# ControllerBoardV2Schematic.net
KiCad netlist of a schematic drawn in Altium Designer
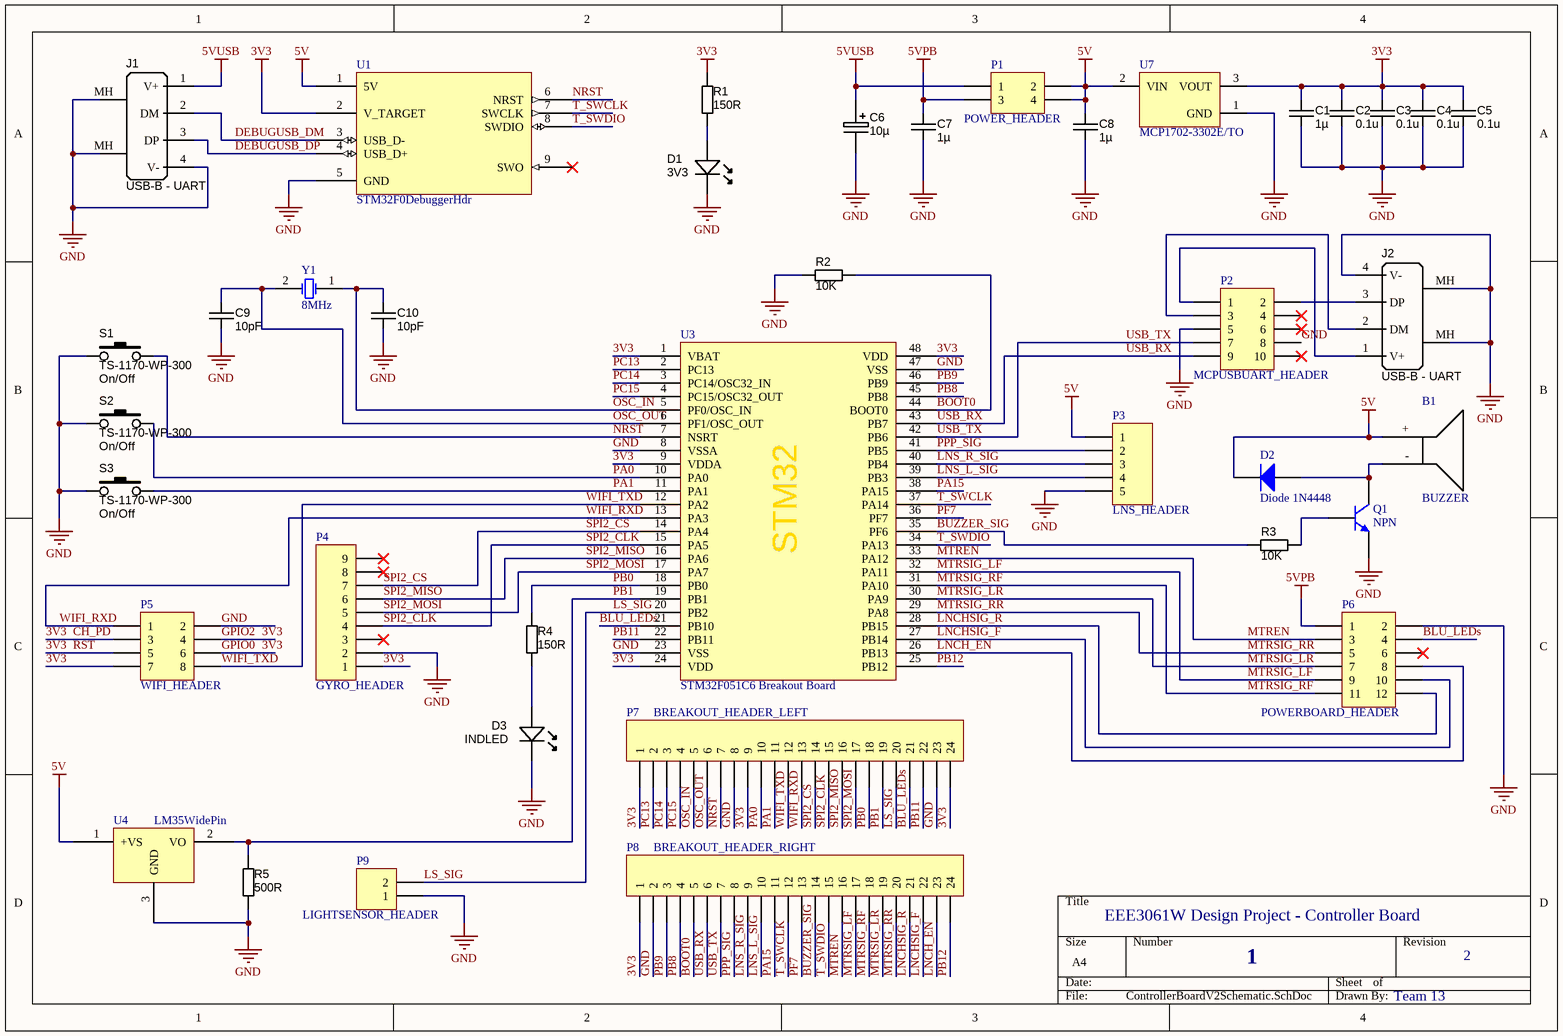
[diagram p0: ControllerBoardV2Schematic.SchDoc]

(export (version "E")
  (design (tool "Eeschema 10.0.6"))
  (components
    (comp (ref "B1")
      (value "BUZZER")
      (footprint "HCM1206UX-G")
      (description "2.3KHz Internally Driven Buzzer")
      (libsource (lib "ControllerBoardCMPV2") (part "HCM1206UX-G"))
    )
    (comp (ref "C1")
      (value "1µ")
      (footprint "CAPC3216X180N")
      (description "Capacitor SMD Cer 10uF 10% 16V X7R 1206")
      (fields (field (name "TOLERANCE") "±10%") (field (name "Comment") "approved sub OK"))
      (libsource (lib "PBL - Capacitors") (part "CAPC_10u_1206_16V"))
    )
    (comp (ref "C2")
      (value "0.1u")
      (footprint "CAPC2012X135N")
      (description "Capacitor SMD Cer 1.8nF 10% 50V X7R 0805")
      (fields (field (name "TOLERANCE") "±10%") (field (name "Comment") "approved sub OK"))
      (libsource (lib "PBL - Capacitors") (part "CAPC_1n8_50V_0805"))
    )
    (comp (ref "C3")
      (value "0.1u")
      (footprint "CAPC2012X135N")
      (description "Capacitor SMD Cer 1.8nF 10% 50V X7R 0805")
      (fields (field (name "TOLERANCE") "±10%") (field (name "Comment") "approved sub OK"))
      (libsource (lib "PBL - Capacitors") (part "CAPC_1n8_50V_0805"))
    )
    (comp (ref "C4")
      (value "0.1u")
      (footprint "CAPC2012X135N")
      (description "Capacitor SMD Cer 1.8nF 10% 50V X7R 0805")
      (fields (field (name "TOLERANCE") "±10%") (field (name "Comment") "approved sub OK"))
      (libsource (lib "PBL - Capacitors") (part "CAPC_1n8_50V_0805"))
    )
    (comp (ref "C5")
      (value "0.1u")
      (footprint "CAPC2012X135N")
      (description "Capacitor SMD Cer 1.8nF 10% 50V X7R 0805")
      (fields (field (name "TOLERANCE") "±10%") (field (name "Comment") "approved sub OK"))
      (libsource (lib "PBL - Capacitors") (part "CAPC_1n8_50V_0805"))
    )
    (comp (ref "C6")
      (value "10µ")
      (footprint "CAPR5-4X5")
      (description "Capacitor THT Alum Elec 220uF 20% 16V 2.5mmLS")
      (fields (field (name "TOLERANCE") "±20%"))
      (libsource (lib "PBL - Capacitors") (part "CAPE_220u_16V_THD_2.5mmLS"))
    )
    (comp (ref "C7")
      (value "1µ")
      (footprint "CAPC3216X180N")
      (description "Capacitor SMD Cer 10uF 10% 16V X7R 1206")
      (fields (field (name "TOLERANCE") "±10%") (field (name "Comment") "approved sub OK"))
      (libsource (lib "PBL - Capacitors") (part "CAPC_10u_1206_16V"))
    )
    (comp (ref "C8")
      (value "1µ")
      (footprint "CAPC3216X180N")
      (description "Capacitor SMD Cer 10uF 10% 16V X7R 1206")
      (fields (field (name "TOLERANCE") "±10%") (field (name "Comment") "approved sub OK"))
      (libsource (lib "PBL - Capacitors") (part "CAPC_10u_1206_16V"))
    )
    (comp (ref "C9")
      (value "10pF")
      (footprint "CAPC2012X135N")
      (description "Capacitor SMD Cer 1.8nF 10% 50V X7R 0805")
      (fields (field (name "TOLERANCE") "±10%") (field (name "Comment") "approved sub OK"))
      (libsource (lib "PBL - Capacitors") (part "CAPC_1n8_50V_0805"))
    )
    (comp (ref "C10")
      (value "10pF")
      (footprint "CAPC2012X135N")
      (description "Capacitor SMD Cer 1.8nF 10% 50V X7R 0805")
      (fields (field (name "TOLERANCE") "±10%") (field (name "Comment") "approved sub OK"))
      (libsource (lib "PBL - Capacitors") (part "CAPC_1n8_50V_0805"))
    )
    (comp (ref "D1")
      (value "3V3LED")
      (footprint "LED-0805-K")
      (description "LED, 0805 SMD, Green")
      (fields (field (name "COLOR") "3V3"))
      (libsource (lib "PBL - Light Sources") (part "LED_SMD_Green_0805_6mcd"))
    )
    (comp (ref "D2")
      (value "Diode 1N4448")
      (footprint "DO-35")
      (description "High Conductance Fast Diode")
      (fields (field (name "PUBLISHER") "Altium Limited"))
      (libsource (lib "Miscellaneous Devices") (part "Diode 1N4448"))
    )
    (comp (ref "D3")
      (value "INDLED")
      (footprint "LED-0805-K")
      (description "LED, 0805 SMD, Green")
      (fields (field (name "COLOR") "INDLED"))
      (libsource (lib "PBL - Light Sources") (part "LED_SMD_Green_0805_6mcd"))
    )
    (comp (ref "J1")
      (value "USB-B - UART")
      (footprint "USB_TypeB_Tyco")
      (description "Connector THT Type B USB connector")
      (libsource (lib "PBL - Connectors") (part "USB_TypeB"))
    )
    (comp (ref "J2")
      (value "USB-B - UART")
      (footprint "USB_TypeB_Tyco")
      (description "Connector THT Type B USB connector")
      (libsource (lib "PBL - Connectors") (part "USB_TypeB"))
    )
    (comp (ref "P1")
      (value "POWER_HEADER")
      (footprint "HDR2X2")
      (description "Header, 2-Pin, Dual row")
      (fields (field (name "PUBLISHER") "Altium Limited"))
      (libsource (lib "Miscellaneous Connectors") (part "Header 2X2"))
    )
    (comp (ref "P2")
      (value "MCPUSBUART_HEADER")
      (footprint "HDR2X5")
      (description "Header, 5-Pin, Dual row")
      (fields (field (name "PUBLISHER") "Altium Limited"))
      (libsource (lib "Miscellaneous Connectors") (part "Header 5X2"))
    )
    (comp (ref "P3")
      (value "LNS_HEADER")
      (footprint "HDR1X5")
      (description "Header, 5-Pin")
      (fields (field (name "PUBLISHER") "Altium Limited"))
      (libsource (lib "Miscellaneous Connectors") (part "Header 5"))
    )
    (comp (ref "P4")
      (value "GYRO_HEADER")
      (footprint "HDR1X9")
      (description "Header, 9-Pin")
      (fields (field (name "PUBLISHER") "Altium Limited"))
      (libsource (lib "Miscellaneous Connectors") (part "Header 9"))
    )
    (comp (ref "P5")
      (value "WIFI_HEADER")
      (footprint "HDR2X4")
      (description "Header, 4-Pin, Dual row")
      (fields (field (name "PUBLISHER") "Altium Limited"))
      (libsource (lib "Miscellaneous Connectors") (part "Header 4X2"))
    )
    (comp (ref "P6")
      (value "POWERBOARD_HEADER")
      (footprint "HDR2X6")
      (description "Header, 6-Pin, Dual row")
      (fields (field (name "PUBLISHER") "Altium Limited"))
      (libsource (lib "Miscellaneous Connectors") (part "Header 6X2"))
    )
    (comp (ref "P7")
      (value "BREAKOUT_HEADER_LEFT")
      (footprint "HDR1X24")
      (description "Header, 24-Pin")
      (fields (field (name "PUBLISHER") "Altium Limited"))
      (libsource (lib "Miscellaneous Connectors") (part "Header 24"))
    )
    (comp (ref "P8")
      (value "BREAKOUT_HEADER_RIGHT")
      (footprint "HDR1X24")
      (description "Header, 24-Pin")
      (fields (field (name "PUBLISHER") "Altium Limited"))
      (libsource (lib "Miscellaneous Connectors") (part "Header 24"))
    )
    (comp (ref "P9")
      (value "LIGHTSENSOR_HEADER")
      (footprint "HDR1X2")
      (description "Header, 2-Pin")
      (fields (field (name "PUBLISHER") "Altium Limited"))
      (libsource (lib "Miscellaneous Connectors") (part "Header 2"))
    )
    (comp (ref "Q1")
      (value "NPN")
      (footprint "TO-226-AA")
      (description "NPN Bipolar Transistor")
      (fields (field (name "PUBLISHER") "Altium Limited"))
      (libsource (lib "Miscellaneous Devices") (part "NPN"))
    )
    (comp (ref "R1")
      (value "150R")
      (footprint "RESC2012X70N")
      (description "Resistor SMD chip 150 Ohm 0.125W 5% 0805")
      (fields (field (name "TOLERANCE") "±5%") (field (name "Comment") "Thick Film"))
      (libsource (lib "PBL - Resistors") (part "RES_150R_0805_5%"))
    )
    (comp (ref "R2")
      (value "10K")
      (footprint "RESC2012X70N")
      (description "Resistor SMD chip 150 Ohm 0.125W 5% 0805")
      (fields (field (name "TOLERANCE") "±5%") (field (name "Comment") "Thick Film"))
      (libsource (lib "") (part "RES_150R_0805_5%_1"))
    )
    (comp (ref "R3")
      (value "10K")
      (footprint "RESC2012X70N")
      (description "Resistor SMD chip 150 Ohm 0.125W 5% 0805")
      (fields (field (name "TOLERANCE") "±5%") (field (name "Comment") "Thick Film"))
      (libsource (lib "") (part "RES_150R_0805_5%_1"))
    )
    (comp (ref "R4")
      (value "150R")
      (footprint "RESC2012X70N")
      (description "Resistor SMD chip 150 Ohm 0.125W 5% 0805")
      (fields (field (name "TOLERANCE") "±5%") (field (name "Comment") "Thick Film"))
      (libsource (lib "PBL - Resistors") (part "RES_150R_0805_5%"))
    )
    (comp (ref "R5")
      (value "500R")
      (footprint "RESC2012X70N")
      (description "Resistor SMD chip 150 Ohm 0.125W 5% 0805")
      (fields (field (name "TOLERANCE") "±5%") (field (name "Comment") "Thick Film"))
      (libsource (lib "PBL - Resistors") (part "RES_150R_0805_5%"))
    )
    (comp (ref "S1")
      (value "SW_THT_PB_7.0mm")
      (footprint "TACT-SWITCH-TS1170")
      (description "Switch, tact, 7.0mm stem")
      (fields (field (name "MANUFACTURER PART NUMBER 1") "TS-1170-WP-300") (field (name "FUNCTION") "On/Off"))
      (libsource (lib "PBL - Switches") (part "SW_THT_PB_7.0mm"))
    )
    (comp (ref "S2")
      (value "SW_THT_PB_7.0mm")
      (footprint "TACT-SWITCH-TS1170")
      (description "Switch, tact, 7.0mm stem")
      (fields (field (name "MANUFACTURER PART NUMBER 1") "TS-1170-WP-300") (field (name "FUNCTION") "On/Off"))
      (libsource (lib "PBL - Switches") (part "SW_THT_PB_7.0mm"))
    )
    (comp (ref "S3")
      (value "SW_THT_PB_7.0mm")
      (footprint "TACT-SWITCH-TS1170")
      (description "Switch, tact, 7.0mm stem")
      (fields (field (name "MANUFACTURER PART NUMBER 1") "TS-1170-WP-300") (field (name "FUNCTION") "On/Off"))
      (libsource (lib "PBL - Switches") (part "SW_THT_PB_7.0mm"))
    )
    (comp (ref "U1")
      (value "STM32F0DebuggerHdr")
      (footprint "STM32F051C6_DbgrHdr")
      (libsource (lib "STM32F051C6Breakout") (part "STM32F0DebuggerHdr"))
    )
    (comp (ref "U3")
      (value "STM32F051C6 Breakout Board")
      (footprint "STM32F051C6BreakoutBoard")
      (libsource (lib "STM32F051C6Breakout") (part "STM32F051C6Brk"))
    )
    (comp (ref "U4")
      (value "LM35WidePin")
      (footprint "TO-92Wide")
      (libsource (lib "STM32F051C6Breakout") (part "LM35Big"))
    )
    (comp (ref "U7")
      (value "MCP1702-3302E/TO")
      (footprint "TO-92-TO3")
      (description "250 mA Low Quiescent Current LDO Regulator, 3-Pin TO-92, Extended TemperatureBAG")
      (libsource (lib "Altium Content Vault") (part "CMP-0136-00017-1"))
    )
    (comp (ref "Y1")
      (value "8MHz")
      (footprint "8MHZOSC")
      (description "Crystal Oscillator")
      (fields (field (name "PUBLISHER") "Altium Limited"))
      (libsource (lib "Miscellaneous Devices") (part "XTAL"))
    )
  )
  (nets
    (net (code "1") (name "/BLU_LEDs") (class "Default")
      (node (ref "P6") (pin "4") (pinfunction "4_4") (pintype "passive"))
      (node (ref "P7") (pin "21") (pinfunction "21_21") (pintype "passive"))
      (node (ref "U3") (pin "21") (pinfunction "PB10_21") (pintype "passive"))
    )
    (net (code "2") (name "/BOOT0") (class "Default")
      (node (ref "P8") (pin "5") (pinfunction "5_5") (pintype "passive"))
      (node (ref "R2") (pin "2") (pinfunction "2_2") (pintype "passive"))
      (node (ref "U3") (pin "44") (pinfunction "BOOT0_44") (pintype "passive"))
    )
    (net (code "3") (name "/BUZZER_SIG") (class "Default")
      (node (ref "P8") (pin "14") (pinfunction "14_14") (pintype "passive"))
      (node (ref "R3") (pin "1") (pinfunction "1_1") (pintype "passive"))
      (node (ref "U3") (pin "35") (pinfunction "PF6_35") (pintype "passive"))
    )
    (net (code "4") (name "/DEBUGUSB_DM") (class "Default")
      (node (ref "J1") (pin "2") (pinfunction "DM_2") (pintype "passive"))
      (node (ref "U1") (pin "3") (pinfunction "USB_D-_3") (pintype "bidirectional"))
    )
    (net (code "5") (name "/DEBUGUSB_DP") (class "Default")
      (node (ref "J1") (pin "3") (pinfunction "DP_3") (pintype "passive"))
      (node (ref "U1") (pin "4") (pinfunction "USB_D+_4") (pintype "bidirectional"))
    )
    (net (code "6") (name "/LNCHSIG_F") (class "Default")
      (node (ref "P6") (pin "10") (pinfunction "10_10") (pintype "passive"))
      (node (ref "P8") (pin "22") (pinfunction "22_22") (pintype "passive"))
      (node (ref "U3") (pin "27") (pinfunction "PB14_27") (pintype "passive"))
    )
    (net (code "7") (name "/LNCHSIG_R") (class "Default")
      (node (ref "P6") (pin "12") (pinfunction "12_12") (pintype "passive"))
      (node (ref "P8") (pin "21") (pinfunction "21_21") (pintype "passive"))
      (node (ref "U3") (pin "28") (pinfunction "PB15_28") (pintype "passive"))
    )
    (net (code "8") (name "/LNCH_EN") (class "Default")
      (node (ref "P6") (pin "8") (pinfunction "8_8") (pintype "passive"))
      (node (ref "P8") (pin "23") (pinfunction "23_23") (pintype "passive"))
      (node (ref "U3") (pin "26") (pinfunction "PB13_26") (pintype "passive"))
    )
    (net (code "9") (name "/LNS_L_SIG") (class "Default")
      (node (ref "P3") (pin "4") (pinfunction "4_4") (pintype "passive"))
      (node (ref "P8") (pin "10") (pinfunction "10_10") (pintype "passive"))
      (node (ref "U3") (pin "39") (pinfunction "PB3_39") (pintype "passive"))
    )
    (net (code "10") (name "/LNS_R_SIG") (class "Default")
      (node (ref "P3") (pin "3") (pinfunction "3_3") (pintype "passive"))
      (node (ref "P8") (pin "9") (pinfunction "9_9") (pintype "passive"))
      (node (ref "U3") (pin "40") (pinfunction "PB4_40") (pintype "passive"))
    )
    (net (code "11") (name "/LS_SIG") (class "Default")
      (node (ref "P7") (pin "20") (pinfunction "20_20") (pintype "passive"))
      (node (ref "P9") (pin "2") (pinfunction "2_2") (pintype "passive"))
      (node (ref "U3") (pin "20") (pinfunction "PB2_20") (pintype "passive"))
    )
    (net (code "12") (name "/MTREN") (class "Default")
      (node (ref "P6") (pin "3") (pinfunction "3_3") (pintype "passive"))
      (node (ref "P8") (pin "16") (pinfunction "16_16") (pintype "passive"))
      (node (ref "U3") (pin "33") (pinfunction "PA12_33") (pintype "passive"))
    )
    (net (code "13") (name "/MTRSIG_LF") (class "Default")
      (node (ref "P6") (pin "9") (pinfunction "9_9") (pintype "passive"))
      (node (ref "P8") (pin "17") (pinfunction "17_17") (pintype "passive"))
      (node (ref "U3") (pin "32") (pinfunction "PA11_32") (pintype "passive"))
    )
    (net (code "14") (name "/MTRSIG_LR") (class "Default")
      (node (ref "P6") (pin "7") (pinfunction "7_7") (pintype "passive"))
      (node (ref "P8") (pin "19") (pinfunction "19_19") (pintype "passive"))
      (node (ref "U3") (pin "30") (pinfunction "PA9_30") (pintype "passive"))
    )
    (net (code "15") (name "/MTRSIG_RF") (class "Default")
      (node (ref "P6") (pin "11") (pinfunction "11_11") (pintype "passive"))
      (node (ref "P8") (pin "18") (pinfunction "18_18") (pintype "passive"))
      (node (ref "U3") (pin "31") (pinfunction "PA10_31") (pintype "passive"))
    )
    (net (code "16") (name "/MTRSIG_RR") (class "Default")
      (node (ref "P6") (pin "5") (pinfunction "5_5") (pintype "passive"))
      (node (ref "P8") (pin "20") (pinfunction "20_20") (pintype "passive"))
      (node (ref "U3") (pin "29") (pinfunction "PA8_29") (pintype "passive"))
    )
    (net (code "17") (name "/NRST") (class "Default")
      (node (ref "P7") (pin "7") (pinfunction "7_7") (pintype "passive"))
      (node (ref "S1") (pin "2") (pintype "passive"))
      (node (ref "U1") (pin "6") (pinfunction "NRST_6") (pintype "output"))
      (node (ref "U3") (pin "7") (pinfunction "NSRT_7") (pintype "passive"))
    )
    (net (code "18") (name "/OSC_IN") (class "Default")
      (node (ref "C10") (pin "1") (pintype "passive"))
      (node (ref "P7") (pin "5") (pinfunction "5_5") (pintype "passive"))
      (node (ref "U3") (pin "5") (pinfunction "PF0/OSC_IN_5") (pintype "passive"))
      (node (ref "Y1") (pin "1") (pinfunction "OSC1_1") (pintype "passive"))
    )
    (net (code "19") (name "/OSC_OUT") (class "Default")
      (node (ref "C9") (pin "1") (pintype "passive"))
      (node (ref "P7") (pin "6") (pinfunction "6_6") (pintype "passive"))
      (node (ref "U3") (pin "6") (pinfunction "PF1/OSC_OUT_6") (pintype "passive"))
      (node (ref "Y1") (pin "2") (pinfunction "OSC2_2") (pintype "passive"))
    )
    (net (code "20") (name "/PA0") (class "Default")
      (node (ref "P7") (pin "10") (pinfunction "10_10") (pintype "passive"))
      (node (ref "S2") (pin "2") (pintype "passive"))
      (node (ref "U3") (pin "10") (pinfunction "PA0_10") (pintype "passive"))
    )
    (net (code "21") (name "/PA1") (class "Default")
      (node (ref "P7") (pin "11") (pinfunction "11_11") (pintype "passive"))
      (node (ref "S3") (pin "2") (pintype "passive"))
      (node (ref "U3") (pin "11") (pinfunction "PA1_11") (pintype "passive"))
    )
    (net (code "22") (name "/PA15") (class "Default")
      (node (ref "P8") (pin "11") (pinfunction "11_11") (pintype "passive"))
      (node (ref "U3") (pin "38") (pinfunction "PA15_38") (pintype "passive"))
    )
    (net (code "23") (name "/PB0") (class "Default")
      (node (ref "P7") (pin "18") (pinfunction "18_18") (pintype "passive"))
      (node (ref "R4") (pin "1") (pinfunction "1_1") (pintype "passive"))
      (node (ref "U3") (pin "18") (pinfunction "PB0_18") (pintype "passive"))
    )
    (net (code "24") (name "/PB1") (class "Default")
      (node (ref "P7") (pin "19") (pinfunction "19_19") (pintype "passive"))
      (node (ref "R5") (pin "1") (pinfunction "1_1") (pintype "passive"))
      (node (ref "U3") (pin "19") (pinfunction "PB1_19") (pintype "passive"))
      (node (ref "U4") (pin "2") (pinfunction "VO_2") (pintype "passive"))
    )
    (net (code "25") (name "/PB8") (class "Default")
      (node (ref "P8") (pin "4") (pinfunction "4_4") (pintype "passive"))
      (node (ref "U3") (pin "45") (pinfunction "PB8_45") (pintype "passive"))
    )
    (net (code "26") (name "/PB9") (class "Default")
      (node (ref "P8") (pin "3") (pinfunction "3_3") (pintype "passive"))
      (node (ref "U3") (pin "46") (pinfunction "PB9_46") (pintype "passive"))
    )
    (net (code "27") (name "/PB11") (class "Default")
      (node (ref "P7") (pin "22") (pinfunction "22_22") (pintype "passive"))
      (node (ref "U3") (pin "22") (pinfunction "PB11_22") (pintype "passive"))
    )
    (net (code "28") (name "/PB12") (class "Default")
      (node (ref "P8") (pin "24") (pinfunction "24_24") (pintype "passive"))
      (node (ref "U3") (pin "25") (pinfunction "PB12_25") (pintype "passive"))
    )
    (net (code "29") (name "/PC13") (class "Default")
      (node (ref "P7") (pin "2") (pinfunction "2_2") (pintype "passive"))
      (node (ref "U3") (pin "2") (pinfunction "PC13_2") (pintype "passive"))
    )
    (net (code "30") (name "/PC14") (class "Default")
      (node (ref "P7") (pin "3") (pinfunction "3_3") (pintype "passive"))
      (node (ref "U3") (pin "3") (pinfunction "PC14/OSC32_IN_3") (pintype "passive"))
    )
    (net (code "31") (name "/PC15") (class "Default")
      (node (ref "P7") (pin "4") (pinfunction "4_4") (pintype "passive"))
      (node (ref "U3") (pin "4") (pinfunction "PC15/OSC32_OUT_4") (pintype "passive"))
    )
    (net (code "32") (name "/PF7") (class "Default")
      (node (ref "P8") (pin "13") (pinfunction "13_13") (pintype "passive"))
      (node (ref "U3") (pin "36") (pinfunction "PF7_36") (pintype "passive"))
    )
    (net (code "33") (name "/PPP_SIG") (class "Default")
      (node (ref "P3") (pin "2") (pinfunction "2_2") (pintype "passive"))
      (node (ref "P8") (pin "8") (pinfunction "8_8") (pintype "passive"))
      (node (ref "U3") (pin "41") (pinfunction "PB5_41") (pintype "passive"))
    )
    (net (code "34") (name "/SPI2_CLK") (class "Default")
      (node (ref "P4") (pin "4") (pinfunction "4_4") (pintype "passive"))
      (node (ref "P7") (pin "15") (pinfunction "15_15") (pintype "passive"))
      (node (ref "U3") (pin "15") (pinfunction "PA5_15") (pintype "passive"))
    )
    (net (code "35") (name "/SPI2_CS") (class "Default")
      (node (ref "P4") (pin "7") (pinfunction "7_7") (pintype "passive"))
      (node (ref "P7") (pin "14") (pinfunction "14_14") (pintype "passive"))
      (node (ref "U3") (pin "14") (pinfunction "PA4_14") (pintype "passive"))
    )
    (net (code "36") (name "/SPI2_MISO") (class "Default")
      (node (ref "P4") (pin "6") (pinfunction "6_6") (pintype "passive"))
      (node (ref "P7") (pin "16") (pinfunction "16_16") (pintype "passive"))
      (node (ref "U3") (pin "16") (pinfunction "PA6_16") (pintype "passive"))
    )
    (net (code "37") (name "/SPI2_MOSI") (class "Default")
      (node (ref "P4") (pin "5") (pinfunction "5_5") (pintype "passive"))
      (node (ref "P7") (pin "17") (pinfunction "17_17") (pintype "passive"))
      (node (ref "U3") (pin "17") (pinfunction "PA7_17") (pintype "passive"))
    )
    (net (code "38") (name "/T_SWCLK") (class "Default")
      (node (ref "P8") (pin "12") (pinfunction "12_12") (pintype "passive"))
      (node (ref "U1") (pin "7") (pinfunction "SWCLK_7") (pintype "output"))
      (node (ref "U3") (pin "37") (pinfunction "PA14_37") (pintype "passive"))
    )
    (net (code "39") (name "/T_SWDIO") (class "Default")
      (node (ref "P8") (pin "15") (pinfunction "15_15") (pintype "passive"))
      (node (ref "U1") (pin "8") (pinfunction "SWDIO_8") (pintype "bidirectional"))
      (node (ref "U3") (pin "34") (pinfunction "PA13_34") (pintype "passive"))
    )
    (net (code "40") (name "/USB_RX") (class "Default")
      (node (ref "P2") (pin "9") (pinfunction "9_9") (pintype "passive"))
      (node (ref "P8") (pin "6") (pinfunction "6_6") (pintype "passive"))
      (node (ref "U3") (pin "43") (pinfunction "PB7_43") (pintype "passive"))
    )
    (net (code "41") (name "/USB_TX") (class "Default")
      (node (ref "P2") (pin "7") (pinfunction "7_7") (pintype "passive"))
      (node (ref "P8") (pin "7") (pinfunction "7_7") (pintype "passive"))
      (node (ref "U3") (pin "42") (pinfunction "PB6_42") (pintype "passive"))
    )
    (net (code "42") (name "/WIFI_RXD") (class "Default")
      (node (ref "P5") (pin "1") (pinfunction "1_1") (pintype "passive"))
      (node (ref "P7") (pin "13") (pinfunction "13_13") (pintype "passive"))
      (node (ref "U3") (pin "13") (pinfunction "PA3_13") (pintype "passive"))
    )
    (net (code "43") (name "/WIFI_TXD") (class "Default")
      (node (ref "P5") (pin "8") (pinfunction "8_8") (pintype "passive"))
      (node (ref "P7") (pin "12") (pinfunction "12_12") (pintype "passive"))
      (node (ref "U3") (pin "12") (pinfunction "PA2_12") (pintype "passive"))
    )
    (net (code "44") (name "3V3") (class "Default")
      (node (ref "C1") (pin "1") (pintype "passive"))
      (node (ref "C2") (pin "1") (pintype "passive"))
      (node (ref "C3") (pin "1") (pintype "passive"))
      (node (ref "C4") (pin "1") (pintype "passive"))
      (node (ref "C5") (pin "1") (pintype "passive"))
      (node (ref "P4") (pin "1") (pinfunction "1_1") (pintype "passive"))
      (node (ref "P5") (pin "3") (pinfunction "3_3") (pintype "passive"))
      (node (ref "P5") (pin "4") (pinfunction "4_4") (pintype "passive"))
      (node (ref "P5") (pin "5") (pinfunction "5_5") (pintype "passive"))
      (node (ref "P5") (pin "6") (pinfunction "6_6") (pintype "passive"))
      (node (ref "P5") (pin "7") (pinfunction "7_7") (pintype "passive"))
      (node (ref "P7") (pin "1") (pinfunction "1_1") (pintype "passive"))
      (node (ref "P7") (pin "24") (pinfunction "24_24") (pintype "passive"))
      (node (ref "P7") (pin "9") (pinfunction "9_9") (pintype "passive"))
      (node (ref "P8") (pin "1") (pinfunction "1_1") (pintype "passive"))
      (node (ref "R1") (pin "1") (pinfunction "1_1") (pintype "passive"))
      (node (ref "U1") (pin "2") (pinfunction "V_TARGET_2") (pintype "passive"))
      (node (ref "U3") (pin "1") (pinfunction "VBAT_1") (pintype "passive"))
      (node (ref "U3") (pin "24") (pinfunction "VDD_24") (pintype "passive"))
      (node (ref "U3") (pin "48") (pinfunction "VDD_48") (pintype "passive"))
      (node (ref "U3") (pin "9") (pinfunction "VDDA_9") (pintype "passive"))
      (node (ref "U7") (pin "3") (pinfunction "VOUT_3") (pintype "power_in"))
    )
    (net (code "45") (name "5V") (class "Default")
      (node (ref "B1") (pin "+") (pinfunction "+_+") (pintype "passive"))
      (node (ref "C8") (pin "1") (pintype "passive"))
      (node (ref "D2") (pin "2") (pinfunction "K_2") (pintype "passive"))
      (node (ref "P1") (pin "2") (pinfunction "2_2") (pintype "passive"))
      (node (ref "P1") (pin "4") (pinfunction "4_4") (pintype "passive"))
      (node (ref "P3") (pin "1") (pinfunction "1_1") (pintype "passive"))
      (node (ref "U1") (pin "1") (pinfunction "5V_1") (pintype "passive"))
      (node (ref "U4") (pin "1") (pinfunction "+VS_1") (pintype "passive"))
      (node (ref "U7") (pin "2") (pinfunction "VIN_2") (pintype "power_in"))
    )
    (net (code "46") (name "5VPB") (class "Default")
      (node (ref "C7") (pin "1") (pintype "passive"))
      (node (ref "P1") (pin "3") (pinfunction "3_3") (pintype "passive"))
      (node (ref "P6") (pin "1") (pinfunction "1_1") (pintype "passive"))
    )
    (net (code "47") (name "5VUSB") (class "Default")
      (node (ref "C6") (pin "1") (pintype "passive"))
      (node (ref "J1") (pin "1") (pinfunction "V+_1") (pintype "passive"))
      (node (ref "P1") (pin "1") (pinfunction "1_1") (pintype "passive"))
    )
    (net (code "48") (name "GND") (class "Default")
      (node (ref "C1") (pin "2") (pintype "passive"))
      (node (ref "C10") (pin "2") (pintype "passive"))
      (node (ref "C2") (pin "2") (pintype "passive"))
      (node (ref "C3") (pin "2") (pintype "passive"))
      (node (ref "C4") (pin "2") (pintype "passive"))
      (node (ref "C5") (pin "2") (pintype "passive"))
      (node (ref "C6") (pin "2") (pintype "passive"))
      (node (ref "C7") (pin "2") (pintype "passive"))
      (node (ref "C8") (pin "2") (pintype "passive"))
      (node (ref "C9") (pin "2") (pintype "passive"))
      (node (ref "D1") (pin "K") (pinfunction "K_K") (pintype "passive"))
      (node (ref "D3") (pin "K") (pinfunction "K_K") (pintype "passive"))
      (node (ref "J1") (pin "4") (pinfunction "V-_4") (pintype "passive"))
      (node (ref "J1") (pin "MH") (pinfunction "Shell_MH") (pintype "passive"))
      (node (ref "J2") (pin "4") (pinfunction "V-_4") (pintype "passive"))
      (node (ref "J2") (pin "MH") (pinfunction "Shell_MH") (pintype "passive"))
      (node (ref "P2") (pin "5") (pinfunction "5_5") (pintype "passive"))
      (node (ref "P2") (pin "8") (pinfunction "8_8") (pintype "passive"))
      (node (ref "P3") (pin "5") (pinfunction "5_5") (pintype "passive"))
      (node (ref "P4") (pin "2") (pinfunction "2_2") (pintype "passive"))
      (node (ref "P5") (pin "2") (pinfunction "2_2") (pintype "passive"))
      (node (ref "P6") (pin "2") (pinfunction "2_2") (pintype "passive"))
      (node (ref "P7") (pin "23") (pinfunction "23_23") (pintype "passive"))
      (node (ref "P7") (pin "8") (pinfunction "8_8") (pintype "passive"))
      (node (ref "P8") (pin "2") (pinfunction "2_2") (pintype "passive"))
      (node (ref "P9") (pin "1") (pinfunction "1_1") (pintype "passive"))
      (node (ref "Q1") (pin "3") (pinfunction "E_3") (pintype "passive"))
      (node (ref "R2") (pin "1") (pinfunction "1_1") (pintype "passive"))
      (node (ref "R5") (pin "2") (pinfunction "2_2") (pintype "passive"))
      (node (ref "S1") (pin "1") (pintype "passive"))
      (node (ref "S2") (pin "1") (pintype "passive"))
      (node (ref "S3") (pin "1") (pintype "passive"))
      (node (ref "U1") (pin "5") (pinfunction "GND_5") (pintype "passive"))
      (node (ref "U3") (pin "23") (pinfunction "VSS_23") (pintype "passive"))
      (node (ref "U3") (pin "47") (pinfunction "VSS_47") (pintype "passive"))
      (node (ref "U3") (pin "8") (pinfunction "VSSA_8") (pintype "passive"))
      (node (ref "U4") (pin "3") (pinfunction "GND_3") (pintype "passive"))
      (node (ref "U7") (pin "1") (pinfunction "GND_1") (pintype "power_in"))
    )
    (net (code "49") (name "Net-(D1-PadA)") (class "Default")
      (node (ref "D1") (pin "A") (pinfunction "A_A") (pintype "passive"))
      (node (ref "R1") (pin "2") (pinfunction "2_2") (pintype "passive"))
    )
    (net (code "50") (name "Net-(D2-A)") (class "Default")
      (node (ref "B1") (pin "-") (pinfunction "-_-") (pintype "passive"))
      (node (ref "D2") (pin "1") (pinfunction "A_1") (pintype "passive"))
      (node (ref "Q1") (pin "1") (pinfunction "C_1") (pintype "passive"))
    )
    (net (code "51") (name "Net-(D3-PadA)") (class "Default")
      (node (ref "D3") (pin "A") (pinfunction "A_A") (pintype "passive"))
      (node (ref "R4") (pin "2") (pinfunction "2_2") (pintype "passive"))
    )
    (net (code "52") (name "Net-(J2-DM)") (class "Default")
      (node (ref "J2") (pin "2") (pinfunction "DM_2") (pintype "passive"))
      (node (ref "P2") (pin "3") (pinfunction "3_3") (pintype "passive"))
    )
    (net (code "53") (name "Net-(J2-DP)") (class "Default")
      (node (ref "J2") (pin "3") (pinfunction "DP_3") (pintype "passive"))
      (node (ref "P2") (pin "2") (pinfunction "2_2") (pintype "passive"))
    )
    (net (code "54") (name "Net-(J2-V+)") (class "Default")
      (node (ref "J2") (pin "1") (pinfunction "V+_1") (pintype "passive"))
      (node (ref "P2") (pin "1") (pinfunction "1_1") (pintype "passive"))
    )
    (net (code "55") (name "Net-(Q1-B)") (class "Default")
      (node (ref "Q1") (pin "2") (pinfunction "B_2") (pintype "passive"))
      (node (ref "R3") (pin "2") (pinfunction "2_2") (pintype "passive"))
    )
    (net (code "56") (name "unconnected-(P2-Pad4)") (class "Default")
      (node (ref "P2") (pin "4") (pinfunction "4_4") (pintype "passive+no_connect"))
    )
    (net (code "57") (name "unconnected-(P2-Pad6)") (class "Default")
      (node (ref "P2") (pin "6") (pinfunction "6_6") (pintype "passive+no_connect"))
    )
    (net (code "58") (name "unconnected-(P2-Pad10)") (class "Default")
      (node (ref "P2") (pin "10") (pinfunction "10_10") (pintype "passive+no_connect"))
    )
    (net (code "59") (name "unconnected-(P4-Pad3)") (class "Default")
      (node (ref "P4") (pin "3") (pinfunction "3_3") (pintype "passive+no_connect"))
    )
    (net (code "60") (name "unconnected-(P4-Pad8)") (class "Default")
      (node (ref "P4") (pin "8") (pinfunction "8_8") (pintype "passive+no_connect"))
    )
    (net (code "61") (name "unconnected-(P4-Pad9)") (class "Default")
      (node (ref "P4") (pin "9") (pinfunction "9_9") (pintype "passive+no_connect"))
    )
    (net (code "62") (name "unconnected-(P6-Pad6)") (class "Default")
      (node (ref "P6") (pin "6") (pinfunction "6_6") (pintype "passive+no_connect"))
    )
    (net (code "63") (name "unconnected-(U1-SWO-Pad9)") (class "Default")
      (node (ref "U1") (pin "9") (pinfunction "SWO_9") (pintype "input+no_connect"))
    )
  )
)
